# viraj-hello-ftdi-44.net
KiCad netlist of a schematic drawn in EAGLE
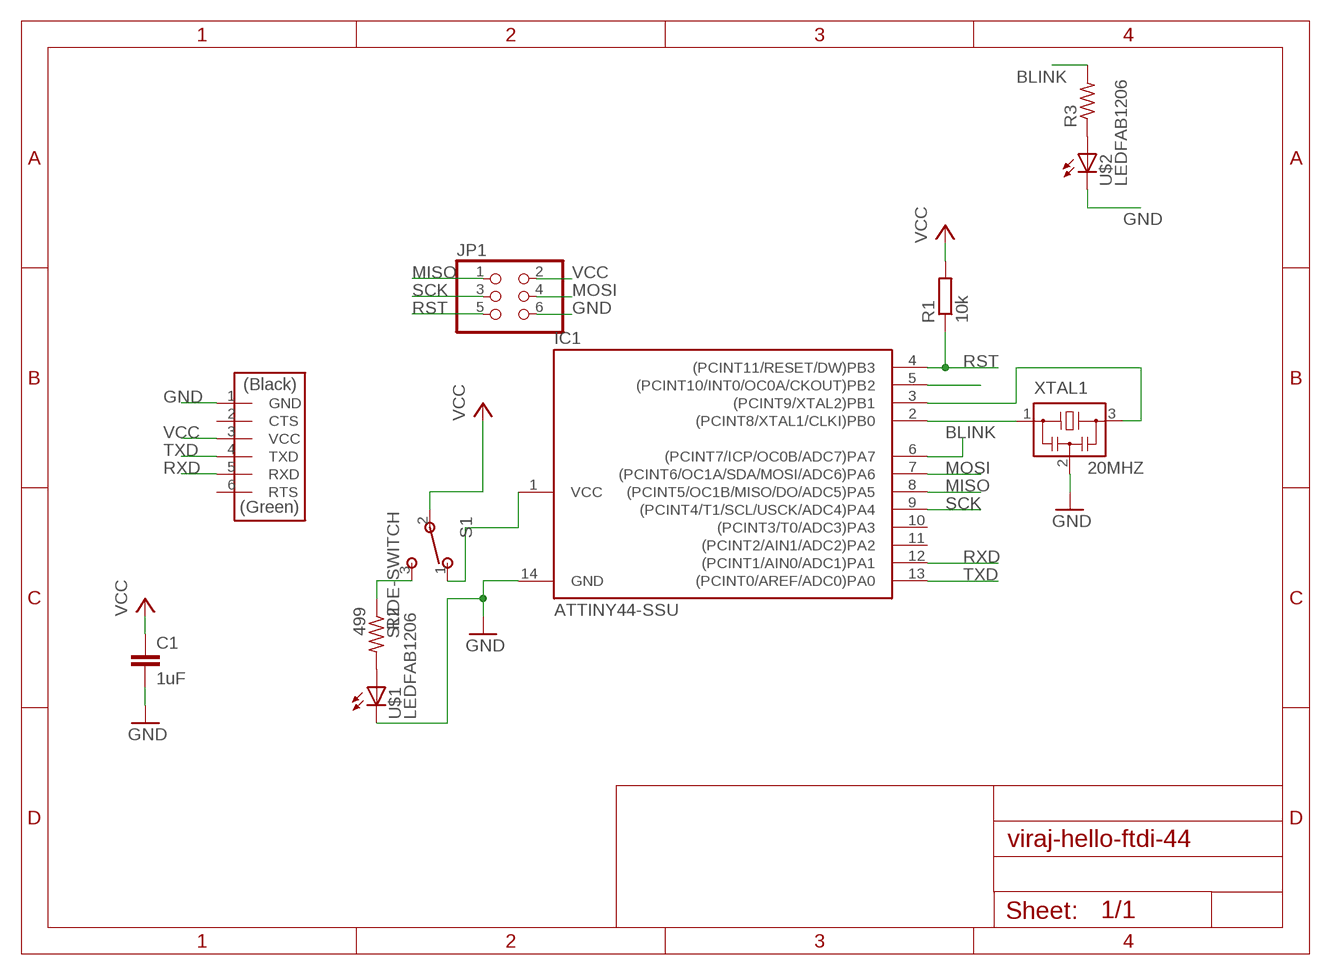
[diagram p0: schematic, sheet 1]

(export (version "E")
  (design (tool "Eeschema 10.0.6"))
  (components
    (comp (ref "C1")
      (value "1uF")
      (footprint "eagle-import:C1206")
      (libsource (lib "eagle-import") (part "C-EUC1206"))
    )
    (comp (ref "IC1")
      (value "ATTINY44-SSU")
      (footprint "eagle-import:SOIC14")
      (libsource (lib "eagle-import") (part "ATTINY44-SSU"))
    )
    (comp (ref "J2")
      (value "FTDI-SMD-HEADER")
      (footprint "eagle-import:1X06SMD")
      (libsource (lib "eagle-import") (part "FTDI-SMD-HEADER"))
    )
    (comp (ref "JP1")
      (value "PINHD-2X3-SMD")
      (footprint "eagle-import:2X03SMD")
      (libsource (lib "eagle-import") (part "PINHD-2X3-SMD"))
    )
    (comp (ref "R1")
      (value "10k")
      (footprint "eagle-import:M1206")
      (libsource (lib "eagle-import") (part "R-EU_M1206"))
    )
    (comp (ref "R2")
      (value "499")
      (footprint "eagle-import:R1206FAB")
      (libsource (lib "eagle-import") (part "RES-US1206FAB"))
    )
    (comp (ref "R3")
      (value "RES-US1206FAB")
      (footprint "eagle-import:R1206FAB")
      (libsource (lib "eagle-import") (part "RES-US1206FAB"))
    )
    (comp (ref "S1")
      (value "SLIDE-SWITCH")
      (footprint "eagle-import:AYZ0102AGRLC")
      (libsource (lib "eagle-import") (part "SLIDE-SWITCH"))
    )
    (comp (ref "U$1")
      (value "LEDFAB1206")
      (footprint "eagle-import:LED1206FAB")
      (libsource (lib "eagle-import") (part "LEDFAB1206"))
    )
    (comp (ref "U$2")
      (value "LEDFAB1206")
      (footprint "eagle-import:LED1206FAB")
      (libsource (lib "eagle-import") (part "LEDFAB1206"))
    )
    (comp (ref "XTAL1")
      (value "20MHZ")
      (footprint "eagle-import:EFOBM")
      (libsource (lib "eagle-import") (part "RESONATOR"))
    )
  )
  (nets
    (net (code "1") (name "/BLINK") (class "Default")
      (node (ref "IC1") (pin "6") (pinfunction "(PCINT7/ICP/OC0B/ADC7)PA7_6") (pintype "bidirectional"))
      (node (ref "R3") (pin "2") (pinfunction "2_2") (pintype "passive"))
    )
    (net (code "2") (name "/MISO") (class "Default")
      (node (ref "IC1") (pin "8") (pinfunction "(PCINT5/OC1B/MISO/DO/ADC5)PA5_8") (pintype "bidirectional"))
      (node (ref "JP1") (pin "1") (pinfunction "1_1") (pintype "passive"))
    )
    (net (code "3") (name "/MOSI") (class "Default")
      (node (ref "IC1") (pin "7") (pinfunction "(PCINT6/OC1A/SDA/MOSI/ADC6)PA6_7") (pintype "bidirectional"))
      (node (ref "JP1") (pin "4") (pinfunction "4_4") (pintype "passive"))
    )
    (net (code "4") (name "/RST") (class "Default")
      (node (ref "IC1") (pin "4") (pinfunction "(PCINT11/RESET/DW)PB3_4") (pintype "bidirectional"))
      (node (ref "JP1") (pin "5") (pinfunction "5_5") (pintype "passive"))
      (node (ref "R1") (pin "1") (pinfunction "1_1") (pintype "passive"))
    )
    (net (code "5") (name "/RXD") (class "Default")
      (node (ref "IC1") (pin "12") (pinfunction "(PCINT1/AIN0/ADC1)PA1_12") (pintype "bidirectional"))
      (node (ref "J2") (pin "5") (pinfunction "RXD_5") (pintype "bidirectional"))
    )
    (net (code "6") (name "/SCK") (class "Default")
      (node (ref "IC1") (pin "9") (pinfunction "(PCINT4/T1/SCL/USCK/ADC4)PA4_9") (pintype "bidirectional"))
      (node (ref "JP1") (pin "3") (pinfunction "3_3") (pintype "passive"))
    )
    (net (code "7") (name "/TXD") (class "Default")
      (node (ref "IC1") (pin "13") (pinfunction "(PCINT0/AREF/ADC0)PA0_13") (pintype "bidirectional"))
      (node (ref "J2") (pin "4") (pinfunction "TXD_4") (pintype "bidirectional"))
    )
    (net (code "8") (name "GND") (class "Default")
      (node (ref "C1") (pin "2") (pinfunction "2_2") (pintype "passive"))
      (node (ref "IC1") (pin "14") (pinfunction "GND_14") (pintype "power_in"))
      (node (ref "J2") (pin "1") (pinfunction "GND_1") (pintype "bidirectional"))
      (node (ref "JP1") (pin "6") (pinfunction "6_6") (pintype "passive"))
      (node (ref "U$1") (pin "2") (pinfunction "C_2") (pintype "passive"))
      (node (ref "U$2") (pin "2") (pinfunction "C_2") (pintype "passive"))
      (node (ref "XTAL1") (pin "2") (pinfunction "2_2") (pintype "passive"))
    )
    (net (code "9") (name "Net-(IC1-(PCINT8{slash}XTAL1{slash}CLKI)PB0)") (class "Default")
      (node (ref "IC1") (pin "2") (pinfunction "(PCINT8/XTAL1/CLKI)PB0_2") (pintype "bidirectional"))
      (node (ref "XTAL1") (pin "1") (pinfunction "1_1") (pintype "passive"))
    )
    (net (code "10") (name "Net-(IC1-(PCINT9{slash}XTAL2)PB1)") (class "Default")
      (node (ref "IC1") (pin "3") (pinfunction "(PCINT9/XTAL2)PB1_3") (pintype "bidirectional"))
      (node (ref "XTAL1") (pin "3") (pinfunction "3_3") (pintype "passive"))
    )
    (net (code "11") (name "Net-(IC1-VCC)") (class "Default")
      (node (ref "IC1") (pin "1") (pinfunction "VCC_1") (pintype "power_in"))
      (node (ref "S1") (pin "1") (pinfunction "1_1") (pintype "bidirectional"))
    )
    (net (code "12") (name "Net-(R2-Pad1)") (class "Default")
      (node (ref "R2") (pin "1") (pinfunction "1_1") (pintype "passive"))
      (node (ref "S1") (pin "3") (pinfunction "3_3") (pintype "bidirectional"))
    )
    (net (code "13") (name "Net-(U$1-A)") (class "Default")
      (node (ref "R2") (pin "2") (pinfunction "2_2") (pintype "passive"))
      (node (ref "U$1") (pin "1") (pinfunction "A_1") (pintype "passive"))
    )
    (net (code "14") (name "Net-(U$2-A)") (class "Default")
      (node (ref "R3") (pin "1") (pinfunction "1_1") (pintype "passive"))
      (node (ref "U$2") (pin "1") (pinfunction "A_1") (pintype "passive"))
    )
    (net (code "15") (name "VCC") (class "Default")
      (node (ref "C1") (pin "1") (pinfunction "1_1") (pintype "passive"))
      (node (ref "J2") (pin "3") (pinfunction "VCC_3") (pintype "bidirectional"))
      (node (ref "JP1") (pin "2") (pinfunction "2_2") (pintype "passive"))
      (node (ref "R1") (pin "2") (pinfunction "2_2") (pintype "passive"))
      (node (ref "S1") (pin "2") (pinfunction "2_2") (pintype "bidirectional"))
    )
    (net (code "16") (name "unconnected-(IC1-(PCINT2{slash}AIN1{slash}ADC2)PA2-Pad11)") (class "Default")
      (node (ref "IC1") (pin "11") (pinfunction "(PCINT2/AIN1/ADC2)PA2_11") (pintype "bidirectional"))
    )
    (net (code "17") (name "unconnected-(IC1-(PCINT3{slash}T0{slash}ADC3)PA3-Pad10)") (class "Default")
      (node (ref "IC1") (pin "10") (pinfunction "(PCINT3/T0/ADC3)PA3_10") (pintype "bidirectional"))
    )
    (net (code "18") (name "unconnected-(IC1-(PCINT10{slash}INT0{slash}OC0A{slash}CKOUT)PB2-Pad5)") (class "Default")
      (node (ref "IC1") (pin "5") (pinfunction "(PCINT10/INT0/OC0A/CKOUT)PB2_5") (pintype "bidirectional"))
    )
    (net (code "19") (name "unconnected-(J2-CTS-Pad2)") (class "Default")
      (node (ref "J2") (pin "2") (pinfunction "CTS_2") (pintype "bidirectional"))
    )
    (net (code "20") (name "unconnected-(J2-RTS-Pad6)") (class "Default")
      (node (ref "J2") (pin "6") (pinfunction "RTS_6") (pintype "bidirectional"))
    )
  )
)
